# DC_MTR_DVR_SCHEM.net
KiCad netlist of a schematic drawn in Altium Designer
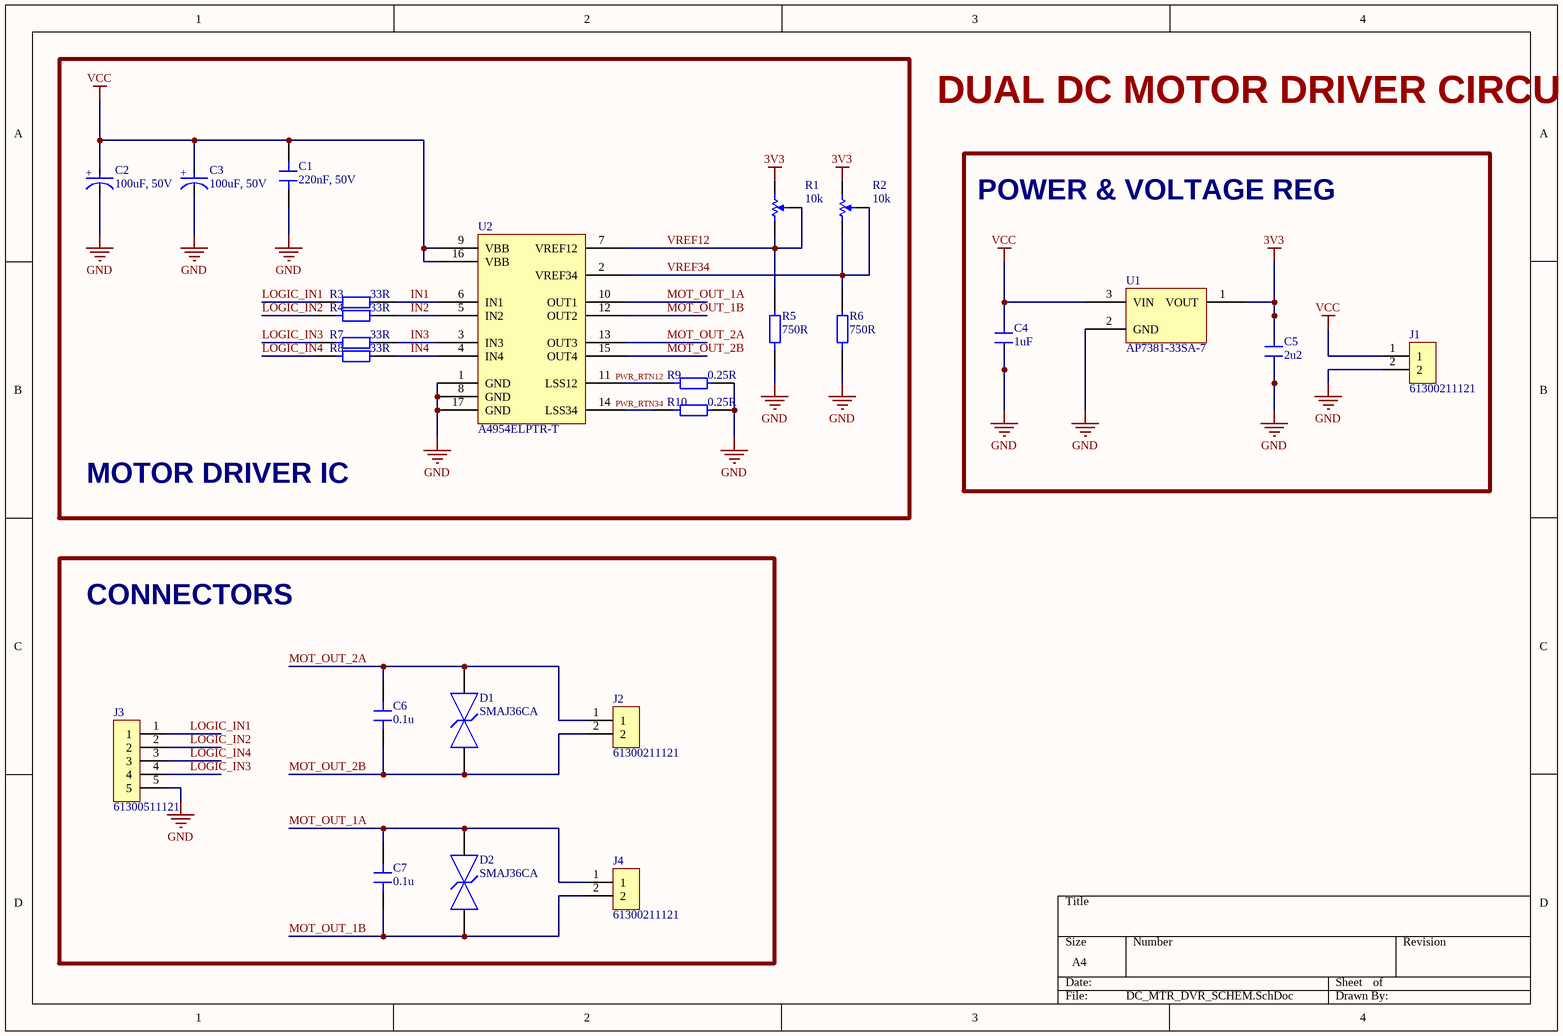
[diagram p0: DC_MTR_DVR_SCHEM.SchDoc]

(export (version "E")
  (design (tool "Eeschema 10.0.6"))
  (components
    (comp (ref "C1")
      (value "220nF, 50V")
      (footprint "FP-0402-L_1_0_0_05-W_0_5-IPC_A")
      (description "CAP CER 0.22UF 50V X5R 0402")
      (fields
        (field (name "MANUFACTURER") "Taiyo Yuden")
        (field (name "MANUFACTURER PART NUMBER") "UMK105BJ224KV-F")
      )
      (libsource (lib "Schlib") (part "UMK105BJ224KV-F"))
    )
    (comp (ref "C2")
      (value "100uF, 50V")
      (footprint "100U_50V_ELECTROLYTIC_CAP")
      (description "CAP ALUM 100UF 20% 50V SMD")
      (fields
        (field (name "MANUFACTURER") "Nichicon")
        (field (name "MANUFACTURER PART NUMBER") "UWT1H101MNL1GS")
      )
      (libsource (lib "Schlib") (part "UWT1H101MNL1GS"))
    )
    (comp (ref "C3")
      (value "100uF, 50V")
      (footprint "100U_50V_ELECTROLYTIC_CAP")
      (description "CAP ALUM 100UF 20% 50V SMD")
      (fields
        (field (name "MANUFACTURER") "Nichicon")
        (field (name "MANUFACTURER PART NUMBER") "UWT1H101MNL1GS")
      )
      (libsource (lib "Schlib") (part "UWT1H101MNL1GS"))
    )
    (comp (ref "C4")
      (value "1uF")
      (footprint "1U_0402_CER_CAP_35V")
      (description "1 µF ±10% 35V Ceramic Capacitor X5R 0402 (1005 Metric)")
      (fields
        (field (name "MANUFACTURER") "TDK")
        (field (name "MANUFACTURER PART NUMBER") "C1005X5R1V105K050BC")
      )
      (libsource (lib "Schlib") (part "C1005X5R1V105K050BC"))
    )
    (comp (ref "C5")
      (value "2u2")
      (footprint "2_2U_0402_CER_CAP")
      (description "CAP CER 2.2UF 35V X5R 0603")
      (fields
        (field (name "MANUFACTURER") "Murata")
        (field (name "MANUFACTURER PART NUMBER") "GRM188R6YA225KA12D")
      )
      (libsource (lib "Schlib") (part "GRM188R6YA225KA12D"))
    )
    (comp (ref "C6")
      (value "0.1u")
      (footprint "1U_0402_CER_CAP_35V")
      (description "CAP CER 0.1UF 35V X5R 0402")
      (fields
        (field (name "MANUFACTURER") "Taiyo Yuden")
        (field (name "MANUFACTURER PART NUMBER") "GMK105BJ104KV-F")
      )
      (libsource (lib "Schlib") (part "GMK105BJ104KV-F"))
    )
    (comp (ref "C7")
      (value "0.1u")
      (footprint "1U_0402_CER_CAP_35V")
      (description "CAP CER 0.1UF 35V X5R 0402")
      (fields
        (field (name "MANUFACTURER") "Taiyo Yuden")
        (field (name "MANUFACTURER PART NUMBER") "GMK105BJ104KV-F")
      )
      (libsource (lib "Schlib") (part "GMK105BJ104KV-F"))
    )
    (comp (ref "D1")
      (value "SMAJ36CA")
      (footprint "TVS_DIODE")
      (description "TVS DIODE 36VWM 58.1VC DO214AC")
      (fields (field (name "MANUFACTURER") "Littelfuse") (field (name "LCSC PART NO.") "C908830"))
      (libsource (lib "Schlib") (part "SMAJ36CA"))
    )
    (comp (ref "D2")
      (value "SMAJ36CA")
      (footprint "TVS_DIODE")
      (description "TVS DIODE 36VWM 58.1VC DO214AC")
      (fields (field (name "MANUFACTURER") "Littelfuse") (field (name "LCSC PART NO.") "C908830"))
      (libsource (lib "Schlib") (part "SMAJ36CA"))
    )
    (comp (ref "J1")
      (value "61300211121")
      (footprint "2_POS_HEADER_2_54")
      (description "CONN HEADER VERT 2POS 2.54MM")
      (fields (field (name "MANUFACTURER") "Wurth Electronics"))
      (libsource (lib "Schlib") (part "61300211121"))
    )
    (comp (ref "J2")
      (value "61300211121")
      (footprint "2_POS_HEADER_2_54")
      (description "CONN HEADER VERT 2POS 2.54MM")
      (fields (field (name "MANUFACTURER") "Wurth Electronics"))
      (libsource (lib "Schlib") (part "61300211121"))
    )
    (comp (ref "J3")
      (value "61300511121")
      (footprint "5_POS_HEADER_2_54")
      (description "CONN HEADER VERT 5POS 2.54MM")
      (fields (field (name "MANUFACTURER") "Wurth Electronics"))
      (libsource (lib "Schlib") (part "61300511121"))
    )
    (comp (ref "J4")
      (value "61300211121")
      (footprint "2_POS_HEADER_2_54")
      (description "CONN HEADER VERT 2POS 2.54MM")
      (fields (field (name "MANUFACTURER") "Wurth Electronics"))
      (libsource (lib "Schlib") (part "61300211121"))
    )
    (comp (ref "R1")
      (value "10k")
      (footprint "10K_TRIM_POT")
      (description "TRIMMER 10K OHM 0.15W J LEAD TOP")
      (fields (field (name "MANUFACTURER") "Bourns") (field (name "MANUFACTURER PART NUMBER") "TC33X-2-103E"))
      (libsource (lib "Schlib") (part "TC33X-2-103E"))
    )
    (comp (ref "R2")
      (value "10k")
      (footprint "10K_TRIM_POT")
      (description "TRIMMER 10K OHM 0.15W J LEAD TOP")
      (fields (field (name "MANUFACTURER") "Bourns") (field (name "MANUFACTURER PART NUMBER") "TC33X-2-103E"))
      (libsource (lib "Schlib") (part "TC33X-2-103E"))
    )
    (comp (ref "R3")
      (value "33R")
      (footprint "33_0402_RES")
      (description "RES 33 OHM 1% 1/16W 0402")
      (fields
        (field (name "MANUFACTURER") "Yageo")
        (field (name "MANUFACTURER PART NUMBER") "RC0402FR-0733RL")
      )
      (libsource (lib "Schlib") (part "RC0402FR-0733RL"))
    )
    (comp (ref "R4")
      (value "33R")
      (footprint "33_0402_RES")
      (description "RES 33 OHM 1% 1/16W 0402")
      (fields
        (field (name "MANUFACTURER") "Yageo")
        (field (name "MANUFACTURER PART NUMBER") "RC0402FR-0733RL")
      )
      (libsource (lib "Schlib") (part "RC0402FR-0733RL"))
    )
    (comp (ref "R5")
      (value "750R")
      (footprint "750_0402_RES")
      (description "RES 750 OHM 5% 1/16W 0402")
      (fields
        (field (name "MANUFACTURER") "Yageo")
        (field (name "MANUFACTURER PART NUMBER") "RC0402JR-07750RL")
      )
      (libsource (lib "Schlib") (part "RC0402JR-07750RL"))
    )
    (comp (ref "R6")
      (value "750R")
      (footprint "750_0402_RES")
      (description "RES 750 OHM 5% 1/16W 0402")
      (fields
        (field (name "MANUFACTURER") "Yageo")
        (field (name "MANUFACTURER PART NUMBER") "RC0402JR-07750RL")
      )
      (libsource (lib "Schlib") (part "RC0402JR-07750RL"))
    )
    (comp (ref "R7")
      (value "33R")
      (footprint "33_0402_RES")
      (description "RES 33 OHM 1% 1/16W 0402")
      (fields
        (field (name "MANUFACTURER") "Yageo")
        (field (name "MANUFACTURER PART NUMBER") "RC0402FR-0733RL")
      )
      (libsource (lib "Schlib") (part "RC0402FR-0733RL"))
    )
    (comp (ref "R8")
      (value "33R")
      (footprint "33_0402_RES")
      (description "RES 33 OHM 1% 1/16W 0402")
      (fields
        (field (name "MANUFACTURER") "Yageo")
        (field (name "MANUFACTURER PART NUMBER") "RC0402FR-0733RL")
      )
      (libsource (lib "Schlib") (part "RC0402FR-0733RL"))
    )
    (comp (ref "R9")
      (value "0.25R")
      (footprint "0_25_RESISTOR")
      (description "RES 0.25 OHM 1% 1/2W 1206")
      (fields
        (field (name "MANUFACTURER") "Stackpole Electronics")
        (field (name "MANUFACTURER PART NUMBER") "CSR1206FKR250")
      )
      (libsource (lib "Schlib") (part "CSR1206FKR250"))
    )
    (comp (ref "R10")
      (value "0.25R")
      (footprint "0_25_RESISTOR")
      (description "RES 0.25 OHM 1% 1/2W 1206")
      (fields
        (field (name "MANUFACTURER") "Stackpole Electronics")
        (field (name "MANUFACTURER PART NUMBER") "CSR1206FKR250")
      )
      (libsource (lib "Schlib") (part "CSR1206FKR250"))
    )
    (comp (ref "U1")
      (value "AP7381-33SA-7")
      (footprint "DIODES INC SOT-89 LINEAR REG")
      (description "IC MOTOR DRIVER 8V-40V 16TSSOP")
      (fields (field (name "MANUFACTURER") "Diodes") (field (name "LCSC PART NO.") "C3752764"))
      (libsource (lib "Schlib") (part "AP7381-33SA-7"))
    )
    (comp (ref "U2")
      (value "A4954ELPTR-T")
      (footprint "ALLEGRO TSSOP-16EP LP")
      (description "IC MOTOR DRIVER 8V-40V 16TSSOP")
      (fields (field (name "MANUFACTURER") "Allegro MicroSystems") (field (name "LCSC PART NO.") "C2688265"))
      (libsource (lib "Schlib") (part "A4954ELPTR-T"))
    )
  )
  (nets
    (net (code "1") (name "/IN1") (class "Default")
      (node (ref "R3") (pin "2") (pinfunction "2_2") (pintype "passive"))
      (node (ref "U2") (pin "6") (pinfunction "IN1_6") (pintype "passive"))
    )
    (net (code "2") (name "/IN2") (class "Default")
      (node (ref "R4") (pin "2") (pinfunction "2_2") (pintype "passive"))
      (node (ref "U2") (pin "5") (pinfunction "IN2_5") (pintype "passive"))
    )
    (net (code "3") (name "/IN3") (class "Default")
      (node (ref "R7") (pin "2") (pinfunction "2_2") (pintype "passive"))
      (node (ref "U2") (pin "3") (pinfunction "IN3_3") (pintype "passive"))
    )
    (net (code "4") (name "/IN4") (class "Default")
      (node (ref "R8") (pin "2") (pinfunction "2_2") (pintype "passive"))
      (node (ref "U2") (pin "4") (pinfunction "IN4_4") (pintype "passive"))
    )
    (net (code "5") (name "/LOGIC_IN1") (class "Default")
      (node (ref "J3") (pin "1") (pinfunction "1_1") (pintype "passive"))
      (node (ref "R3") (pin "1") (pinfunction "1_1") (pintype "passive"))
    )
    (net (code "6") (name "/LOGIC_IN2") (class "Default")
      (node (ref "J3") (pin "2") (pinfunction "2_2") (pintype "passive"))
      (node (ref "R4") (pin "1") (pinfunction "1_1") (pintype "passive"))
    )
    (net (code "7") (name "/LOGIC_IN3") (class "Default")
      (node (ref "J3") (pin "4") (pinfunction "4_4") (pintype "passive"))
      (node (ref "R7") (pin "1") (pinfunction "1_1") (pintype "passive"))
    )
    (net (code "8") (name "/LOGIC_IN4") (class "Default")
      (node (ref "J3") (pin "3") (pinfunction "3_3") (pintype "passive"))
      (node (ref "R8") (pin "1") (pinfunction "1_1") (pintype "passive"))
    )
    (net (code "9") (name "/MOT_OUT_1A") (class "Default")
      (node (ref "C7") (pin "2") (pinfunction "2_2") (pintype "passive"))
      (node (ref "D2") (pin "2") (pinfunction "2_2") (pintype "passive"))
      (node (ref "J4") (pin "1") (pinfunction "1_1") (pintype "passive"))
      (node (ref "U2") (pin "10") (pinfunction "OUT1_10") (pintype "passive"))
    )
    (net (code "10") (name "/MOT_OUT_1B") (class "Default")
      (node (ref "C7") (pin "1") (pinfunction "1_1") (pintype "passive"))
      (node (ref "D2") (pin "1") (pinfunction "1_1") (pintype "passive"))
      (node (ref "J4") (pin "2") (pinfunction "2_2") (pintype "passive"))
      (node (ref "U2") (pin "12") (pinfunction "OUT2_12") (pintype "passive"))
    )
    (net (code "11") (name "/MOT_OUT_2A") (class "Default")
      (node (ref "C6") (pin "2") (pinfunction "2_2") (pintype "passive"))
      (node (ref "D1") (pin "2") (pinfunction "2_2") (pintype "passive"))
      (node (ref "J2") (pin "1") (pinfunction "1_1") (pintype "passive"))
      (node (ref "U2") (pin "13") (pinfunction "OUT3_13") (pintype "passive"))
    )
    (net (code "12") (name "/MOT_OUT_2B") (class "Default")
      (node (ref "C6") (pin "1") (pinfunction "1_1") (pintype "passive"))
      (node (ref "D1") (pin "1") (pinfunction "1_1") (pintype "passive"))
      (node (ref "J2") (pin "2") (pinfunction "2_2") (pintype "passive"))
      (node (ref "U2") (pin "15") (pinfunction "OUT4_15") (pintype "passive"))
    )
    (net (code "13") (name "/PWR_RTN12") (class "Default")
      (node (ref "R9") (pin "1") (pinfunction "1_1") (pintype "passive"))
      (node (ref "U2") (pin "11") (pinfunction "LSS12_11") (pintype "passive"))
    )
    (net (code "14") (name "/PWR_RTN34") (class "Default")
      (node (ref "R10") (pin "1") (pinfunction "1_1") (pintype "passive"))
      (node (ref "U2") (pin "14") (pinfunction "LSS34_14") (pintype "passive"))
    )
    (net (code "15") (name "/VREF12") (class "Default")
      (node (ref "R1") (pin "1") (pinfunction "1_1") (pintype "passive"))
      (node (ref "R1") (pin "2") (pinfunction "2_2") (pintype "passive"))
      (node (ref "R5") (pin "2") (pinfunction "2_2") (pintype "passive"))
      (node (ref "U2") (pin "7") (pinfunction "VREF12_7") (pintype "passive"))
    )
    (net (code "16") (name "/VREF34") (class "Default")
      (node (ref "R2") (pin "1") (pinfunction "1_1") (pintype "passive"))
      (node (ref "R2") (pin "2") (pinfunction "2_2") (pintype "passive"))
      (node (ref "R6") (pin "2") (pinfunction "2_2") (pintype "passive"))
      (node (ref "U2") (pin "2") (pinfunction "VREF34_2") (pintype "passive"))
    )
    (net (code "17") (name "3V3") (class "Default")
      (node (ref "C5") (pin "2") (pinfunction "2_2") (pintype "passive"))
      (node (ref "R1") (pin "3") (pinfunction "3_3") (pintype "passive"))
      (node (ref "R2") (pin "3") (pinfunction "3_3") (pintype "passive"))
      (node (ref "U1") (pin "1") (pinfunction "VOUT_1") (pintype "passive"))
    )
    (net (code "18") (name "GND") (class "Default")
      (node (ref "C1") (pin "1") (pinfunction "1_1") (pintype "passive"))
      (node (ref "C2") (pin "1") (pinfunction "C_1") (pintype "passive"))
      (node (ref "C3") (pin "1") (pinfunction "C_1") (pintype "passive"))
      (node (ref "C4") (pin "1") (pinfunction "1_1") (pintype "passive"))
      (node (ref "C5") (pin "1") (pinfunction "1_1") (pintype "passive"))
      (node (ref "J1") (pin "2") (pinfunction "2_2") (pintype "passive"))
      (node (ref "J3") (pin "5") (pinfunction "5_5") (pintype "passive"))
      (node (ref "R10") (pin "2") (pinfunction "2_2") (pintype "passive"))
      (node (ref "R5") (pin "1") (pinfunction "1_1") (pintype "passive"))
      (node (ref "R6") (pin "1") (pinfunction "1_1") (pintype "passive"))
      (node (ref "R9") (pin "2") (pinfunction "2_2") (pintype "passive"))
      (node (ref "U1") (pin "2") (pinfunction "GND_2") (pintype "passive"))
      (node (ref "U2") (pin "1") (pinfunction "GND_1") (pintype "passive"))
      (node (ref "U2") (pin "17") (pinfunction "GND_17") (pintype "passive"))
      (node (ref "U2") (pin "8") (pinfunction "GND_8") (pintype "passive"))
    )
    (net (code "19") (name "VCC") (class "Default")
      (node (ref "C1") (pin "2") (pinfunction "2_2") (pintype "passive"))
      (node (ref "C2") (pin "2") (pinfunction "A_2") (pintype "passive"))
      (node (ref "C3") (pin "2") (pinfunction "A_2") (pintype "passive"))
      (node (ref "C4") (pin "2") (pinfunction "2_2") (pintype "passive"))
      (node (ref "J1") (pin "1") (pinfunction "1_1") (pintype "passive"))
      (node (ref "U1") (pin "3") (pinfunction "VIN_3") (pintype "passive"))
      (node (ref "U2") (pin "16") (pinfunction "VBB_16") (pintype "passive"))
      (node (ref "U2") (pin "9") (pinfunction "VBB_9") (pintype "passive"))
    )
  )
)
